# MCU_Core.net
KiCad netlist of a schematic drawn in Altium Designer
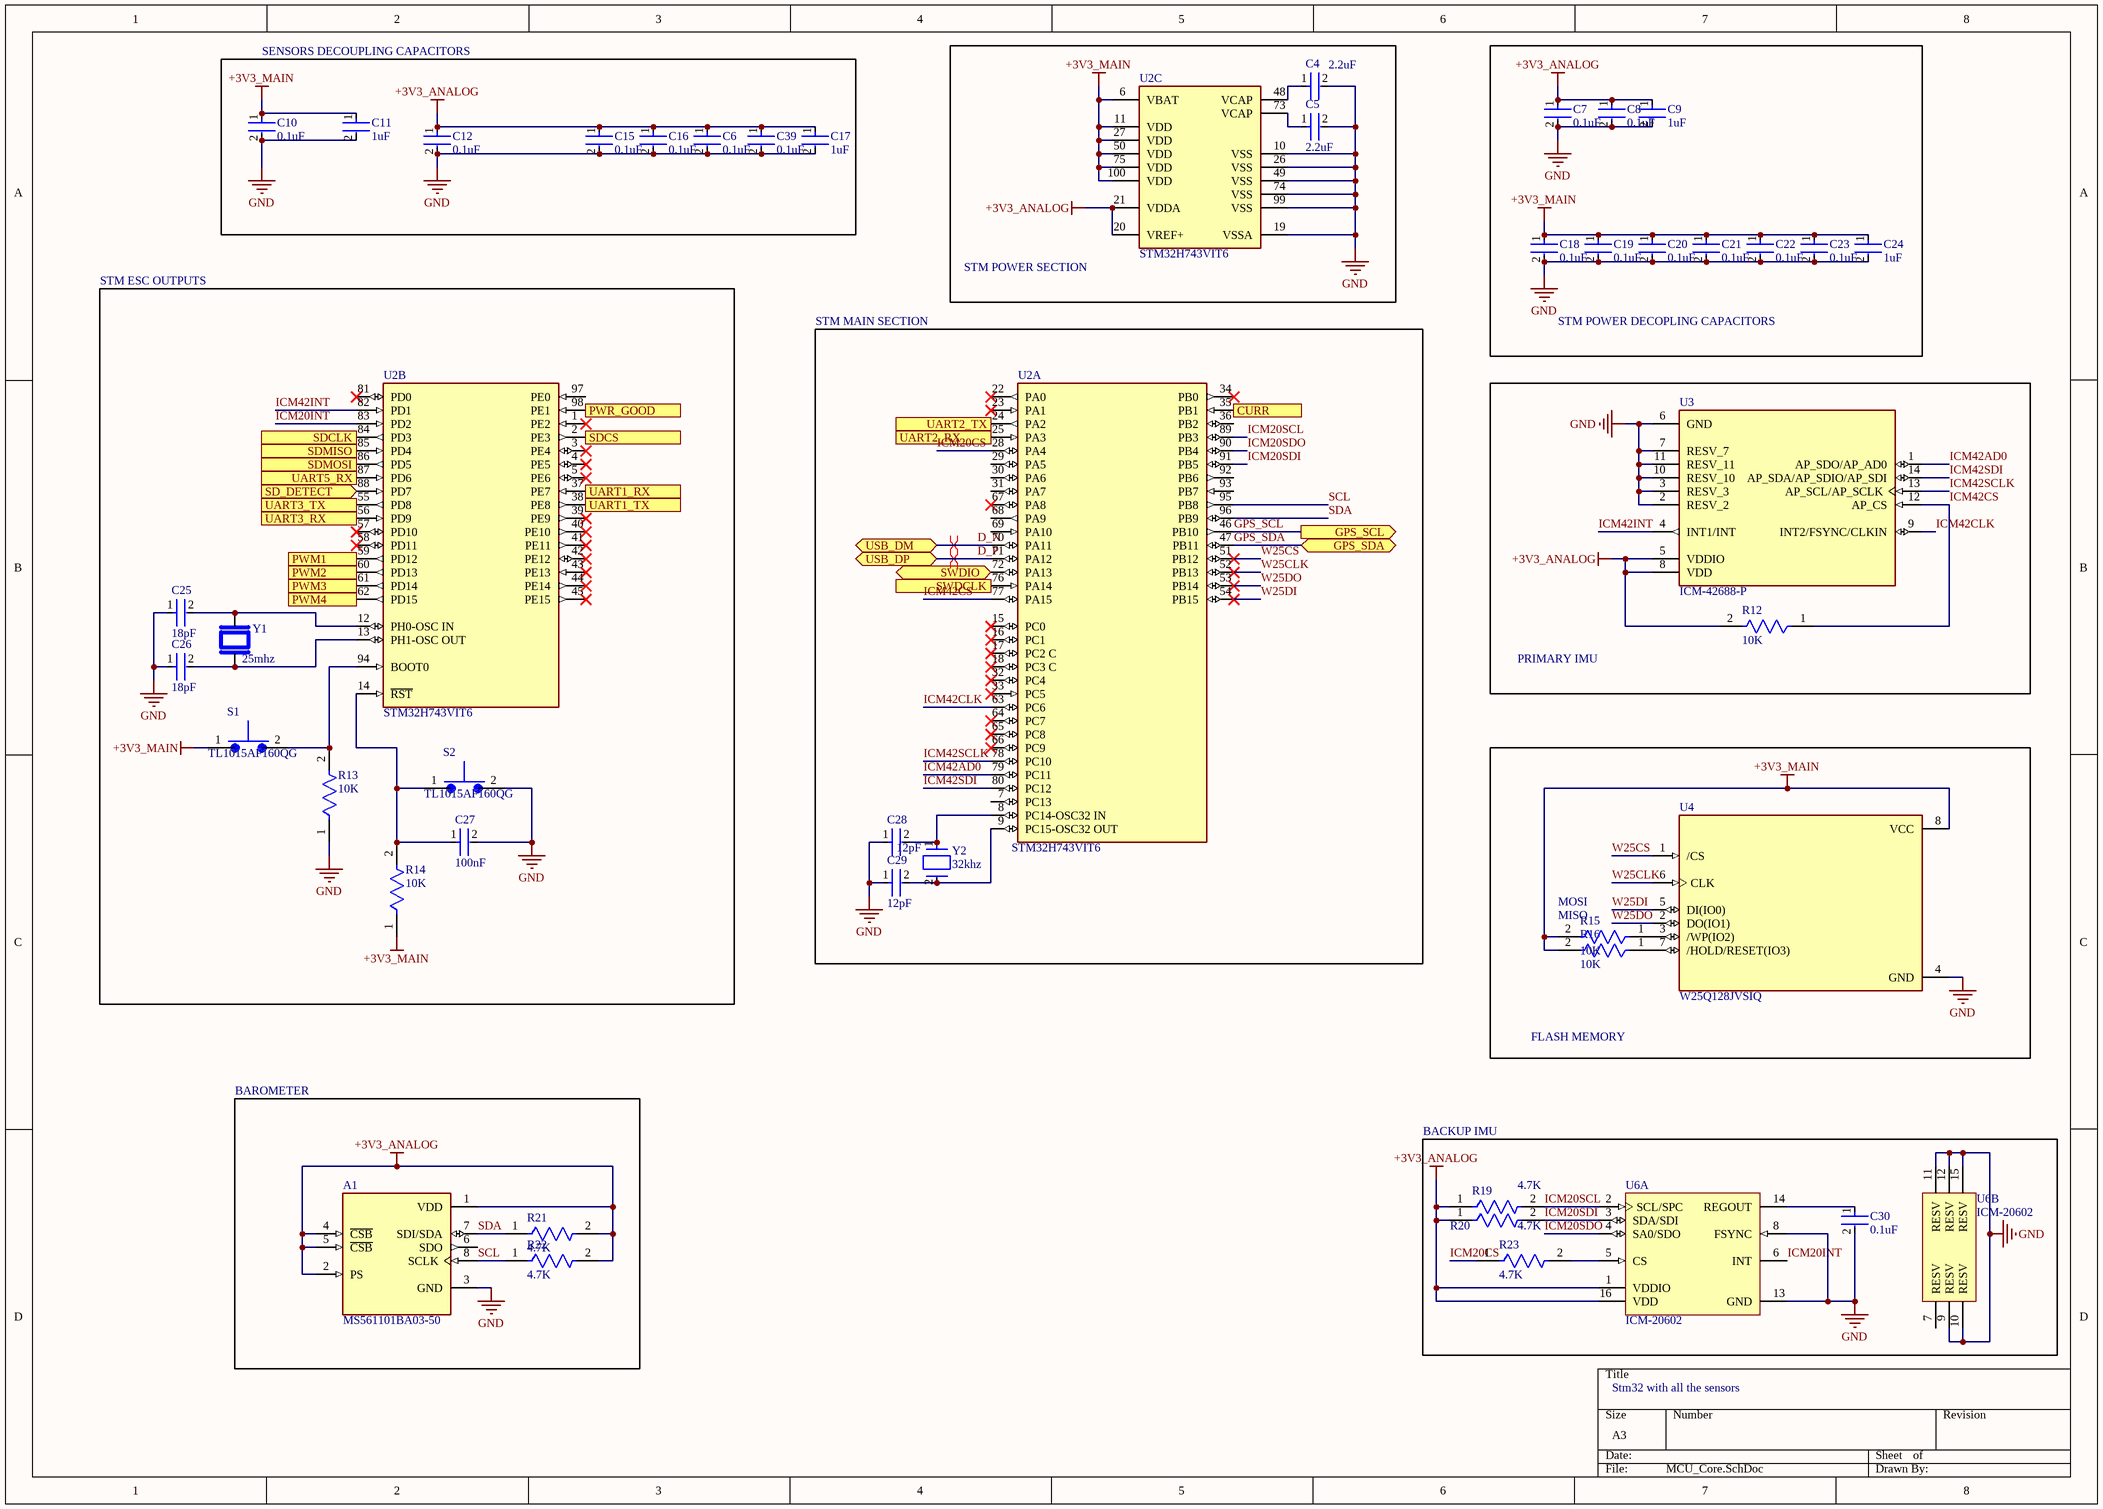
[diagram p0: MCU_Core.SchDoc]

(export (version "E")
  (design (tool "Eeschema 10.0.6"))
  (components
    (comp (ref "A1")
      (value "MS561101BA03-50")
      (footprint "XDCR_MS561101BA03-50")
      (description "Sensor;MS5611-BT M-CAPS 3X5X1MM T&R;Pressure;MS561101BA03-50 ¦ TE Connectivity MS561101BA03-50")
      (fields (field (name "MF") "TE Connectivity"))
      (libsource (lib "MS561101BA03-50") (part "MS561101BA03-50"))
    )
    (comp (ref "C4")
      (value "2.2uF")
      (footprint "FP-GRM155-0_15-IPC_A")
      (description "Chip Multilayer Ceramic Capacitors for General Purpose, 0402, 2.2uF, X7R, 15%, 10%, 10V")
      (libsource (lib "Altium Content Vault") (part "b4654b650e69147ec39a6b967a45e02"))
    )
    (comp (ref "C5")
      (value "2.2uF")
      (footprint "FP-GRM155-0_15-IPC_A")
      (description "Chip Multilayer Ceramic Capacitors for General Purpose, 0402, 2.2uF, X7R, 15%, 10%, 10V")
      (libsource (lib "Altium Content Vault") (part "b4654b650e69147ec39a6b967a45e02"))
    )
    (comp (ref "C6")
      (value "0.1uF")
      (footprint "FP-C0402-BB-MFG")
      (description "CAP CER 0.1UF 10V X7R 0402")
      (fields (field (name "MANUFACTURER") "Kemet") (field (name "TOLERANCE") "0.1"))
      (libsource (lib "Altium Content Vault") (part "b4654b650e69147ec39a6b967a45e02"))
    )
    (comp (ref "C7")
      (value "0.1uF")
      (footprint "FP-C0402-BB-MFG")
      (description "CAP CER 0.1UF 10V X7R 0402")
      (fields (field (name "MANUFACTURER") "Kemet") (field (name "TOLERANCE") "0.1"))
      (libsource (lib "Altium Content Vault") (part "b4654b650e69147ec39a6b967a45e02"))
    )
    (comp (ref "C8")
      (value "0.1uF")
      (footprint "FP-C0402-BB-MFG")
      (description "CAP CER 0.1UF 10V X7R 0402")
      (fields (field (name "MANUFACTURER") "Kemet") (field (name "TOLERANCE") "0.1"))
      (libsource (lib "Altium Content Vault") (part "b4654b650e69147ec39a6b967a45e02"))
    )
    (comp (ref "C9")
      (value "1uF")
      (footprint "FP-GRM152-0_05-MFG")
      (description "Chip Multilayer Ceramic Capacitors for General Purpose, 0402, 1.0uF, X5R, 15%, 20%, 6.3V")
      (fields (field (name "TOLERANCE") "20%"))
      (libsource (lib "Altium Content Vault") (part "b4654b650e69147ec39a6b967a45e02"))
    )
    (comp (ref "C10")
      (value "0.1uF")
      (footprint "FP-C0402-BB-MFG")
      (description "CAP CER 0.1UF 10V X7R 0402")
      (fields (field (name "MANUFACTURER") "Kemet") (field (name "TOLERANCE") "0.1"))
      (libsource (lib "Altium Content Vault") (part "b4654b650e69147ec39a6b967a45e02"))
    )
    (comp (ref "C11")
      (value "1uF")
      (footprint "FP-GRM152-0_05-MFG")
      (description "Chip Multilayer Ceramic Capacitors for General Purpose, 0402, 1.0uF, X5R, 15%, 20%, 6.3V")
      (fields (field (name "TOLERANCE") "20%"))
      (libsource (lib "Altium Content Vault") (part "b4654b650e69147ec39a6b967a45e02"))
    )
    (comp (ref "C12")
      (value "0.1uF")
      (footprint "FP-C0402-BB-MFG")
      (description "CAP CER 0.1UF 10V X7R 0402")
      (fields (field (name "MANUFACTURER") "Kemet") (field (name "TOLERANCE") "0.1"))
      (libsource (lib "Altium Content Vault") (part "b4654b650e69147ec39a6b967a45e02"))
    )
    (comp (ref "C15")
      (value "0.1uF")
      (footprint "FP-C0402-BB-MFG")
      (description "CAP CER 0.1UF 10V X7R 0402")
      (fields (field (name "MANUFACTURER") "Kemet") (field (name "TOLERANCE") "0.1"))
      (libsource (lib "Altium Content Vault") (part "b4654b650e69147ec39a6b967a45e02"))
    )
    (comp (ref "C16")
      (value "0.1uF")
      (footprint "FP-C0402-BB-MFG")
      (description "CAP CER 0.1UF 10V X7R 0402")
      (fields (field (name "MANUFACTURER") "Kemet") (field (name "TOLERANCE") "0.1"))
      (libsource (lib "Altium Content Vault") (part "b4654b650e69147ec39a6b967a45e02"))
    )
    (comp (ref "C17")
      (value "1uF")
      (footprint "FP-GRM152-0_05-MFG")
      (description "Chip Multilayer Ceramic Capacitors for General Purpose, 0402, 1.0uF, X5R, 15%, 20%, 6.3V")
      (fields (field (name "TOLERANCE") "20%"))
      (libsource (lib "Altium Content Vault") (part "b4654b650e69147ec39a6b967a45e02"))
    )
    (comp (ref "C18")
      (value "0.1uF")
      (footprint "FP-C0402-BB-MFG")
      (description "CAP CER 0.1UF 10V X7R 0402")
      (fields (field (name "MANUFACTURER") "Kemet") (field (name "TOLERANCE") "0.1"))
      (libsource (lib "Altium Content Vault") (part "b4654b650e69147ec39a6b967a45e02"))
    )
    (comp (ref "C19")
      (value "0.1uF")
      (footprint "FP-C0402-BB-MFG")
      (description "CAP CER 0.1UF 10V X7R 0402")
      (fields (field (name "MANUFACTURER") "Kemet") (field (name "TOLERANCE") "0.1"))
      (libsource (lib "Altium Content Vault") (part "b4654b650e69147ec39a6b967a45e02"))
    )
    (comp (ref "C20")
      (value "0.1uF")
      (footprint "FP-C0402-BB-MFG")
      (description "CAP CER 0.1UF 10V X7R 0402")
      (fields (field (name "MANUFACTURER") "Kemet") (field (name "TOLERANCE") "0.1"))
      (libsource (lib "Altium Content Vault") (part "b4654b650e69147ec39a6b967a45e02"))
    )
    (comp (ref "C21")
      (value "0.1uF")
      (footprint "FP-C0402-BB-MFG")
      (description "CAP CER 0.1UF 10V X7R 0402")
      (fields (field (name "MANUFACTURER") "Kemet") (field (name "TOLERANCE") "0.1"))
      (libsource (lib "Altium Content Vault") (part "b4654b650e69147ec39a6b967a45e02"))
    )
    (comp (ref "C22")
      (value "0.1uF")
      (footprint "FP-C0402-BB-MFG")
      (description "CAP CER 0.1UF 10V X7R 0402")
      (fields (field (name "MANUFACTURER") "Kemet") (field (name "TOLERANCE") "0.1"))
      (libsource (lib "Altium Content Vault") (part "b4654b650e69147ec39a6b967a45e02"))
    )
    (comp (ref "C23")
      (value "0.1uF")
      (footprint "FP-C0402-BB-MFG")
      (description "CAP CER 0.1UF 10V X7R 0402")
      (fields (field (name "MANUFACTURER") "Kemet") (field (name "TOLERANCE") "0.1"))
      (libsource (lib "Altium Content Vault") (part "b4654b650e69147ec39a6b967a45e02"))
    )
    (comp (ref "C24")
      (value "1uF")
      (footprint "FP-GRM152-0_05-MFG")
      (description "Chip Multilayer Ceramic Capacitors for General Purpose, 0402, 1.0uF, X5R, 15%, 20%, 6.3V")
      (fields (field (name "TOLERANCE") "20%"))
      (libsource (lib "Altium Content Vault") (part "b4654b650e69147ec39a6b967a45e02"))
    )
    (comp (ref "C25")
      (value "18pF")
      (footprint "FP-C0402-BB-MFG")
      (description "C0402 18 pF X8R 5.00% 50 V")
      (fields
        (field (name "OCTOPART") "https://octopart.com/c0402c180j5hacauto-kemet-88080534")
        (field (name "MANUFACTURER") "Kemet")
      )
      (libsource (lib "Altium Content Vault") (part "b4654b650e69147ec39a6b967a45e02"))
    )
    (comp (ref "C26")
      (value "18pF")
      (footprint "FP-C0402-BB-MFG")
      (description "C0402 18 pF X8R 5.00% 50 V")
      (fields
        (field (name "OCTOPART") "https://octopart.com/c0402c180j5hacauto-kemet-88080534")
        (field (name "MANUFACTURER") "Kemet")
      )
      (libsource (lib "Altium Content Vault") (part "b4654b650e69147ec39a6b967a45e02"))
    )
    (comp (ref "C27")
      (value "100nF")
      (footprint "FP-C0402-BB-MFG")
      (description "CAP CER 0.1UF 10V X7R 0402")
      (fields (field (name "MANUFACTURER") "Kemet") (field (name "TOLERANCE") "0.1"))
      (libsource (lib "Altium Content Vault") (part "b4654b650e69147ec39a6b967a45e02"))
    )
    (comp (ref "C28")
      (value "12pF")
      (footprint "FP-C0402-BB-MFG")
      (description "C0402 12 pF X8R 5.00% 50 V")
      (fields (field (name "TOLERANCE") "0.05") (field (name "MANUFACTURER") "Kemet"))
      (libsource (lib "Altium Content Vault") (part "b4654b650e69147ec39a6b967a45e02"))
    )
    (comp (ref "C29")
      (value "12pF")
      (footprint "FP-C0402-BB-MFG")
      (description "C0402 12 pF X8R 5.00% 50 V")
      (fields (field (name "TOLERANCE") "0.05") (field (name "MANUFACTURER") "Kemet"))
      (libsource (lib "Altium Content Vault") (part "b4654b650e69147ec39a6b967a45e02"))
    )
    (comp (ref "C30")
      (value "0.1uF")
      (footprint "FP-C0402-BB-MFG")
      (description "CAP CER 0.1UF 10V X7R 0402")
      (fields (field (name "MANUFACTURER") "Kemet") (field (name "TOLERANCE") "0.1"))
      (libsource (lib "Altium Content Vault") (part "b4654b650e69147ec39a6b967a45e02"))
    )
    (comp (ref "C39")
      (value "0.1uF")
      (footprint "FP-C0402-BB-MFG")
      (description "CAP CER 0.1UF 10V X7R 0402")
      (fields (field (name "MANUFACTURER") "Kemet") (field (name "TOLERANCE") "0.1"))
      (libsource (lib "Altium Content Vault") (part "b4654b650e69147ec39a6b967a45e02"))
    )
    (comp (ref "R12")
      (value "10K")
      (footprint "FP-MCS0402-MFG")
      (description "RES SMD 1.2K OHM 1% 1/10W 0402")
      (fields (field (name "TOLERANCE") "0.5%"))
      (libsource (lib "Altium Content Vault") (part "1029c3af85768c4190bb7ad29bc67b5"))
    )
    (comp (ref "R13")
      (value "10K")
      (footprint "FP-MCS0402-MFG")
      (description "RES SMD 1.2K OHM 1% 1/10W 0402")
      (fields (field (name "TOLERANCE") "0.5%"))
      (libsource (lib "Altium Content Vault") (part "1029c3af85768c4190bb7ad29bc67b5"))
    )
    (comp (ref "R14")
      (value "10K")
      (footprint "FP-MCS0402-MFG")
      (description "RES SMD 1.2K OHM 1% 1/10W 0402")
      (fields (field (name "TOLERANCE") "0.5%"))
      (libsource (lib "Altium Content Vault") (part "1029c3af85768c4190bb7ad29bc67b5"))
    )
    (comp (ref "R15")
      (value "10K")
      (footprint "FP-MCS0402-MFG")
      (description "RES SMD 1.2K OHM 1% 1/10W 0402")
      (fields (field (name "TOLERANCE") "0.5%"))
      (libsource (lib "Altium Content Vault") (part "1029c3af85768c4190bb7ad29bc67b5"))
    )
    (comp (ref "R16")
      (value "10K")
      (footprint "FP-MCS0402-MFG")
      (description "RES SMD 1.2K OHM 1% 1/10W 0402")
      (fields (field (name "TOLERANCE") "0.5%"))
      (libsource (lib "Altium Content Vault") (part "1029c3af85768c4190bb7ad29bc67b5"))
    )
    (comp (ref "R19")
      (value "4.7K")
      (footprint "FP-CRCW0402-Pe3-IPC_C")
      (description "RES Thick Film, 4.7kΩ, 1%, 0.063W, 50ppm/°C, 0402")
      (fields (field (name "TOLERANCE") "1%"))
      (libsource (lib "Altium Content Vault") (part "1029c3af85768c4190bb7ad29bc67b5"))
    )
    (comp (ref "R20")
      (value "4.7K")
      (footprint "FP-CRCW0402-Pe3-IPC_C")
      (description "RES Thick Film, 4.7kΩ, 1%, 0.063W, 50ppm/°C, 0402")
      (fields (field (name "TOLERANCE") "1%"))
      (libsource (lib "Altium Content Vault") (part "1029c3af85768c4190bb7ad29bc67b5"))
    )
    (comp (ref "R21")
      (value "4.7K")
      (footprint "FP-CRCW0402-Pe3-IPC_C")
      (description "RES Thick Film, 4.7kΩ, 1%, 0.063W, 50ppm/°C, 0402")
      (fields (field (name "TOLERANCE") "1%"))
      (libsource (lib "Altium Content Vault") (part "1029c3af85768c4190bb7ad29bc67b5"))
    )
    (comp (ref "R22")
      (value "4.7K")
      (footprint "FP-CRCW0402-Pe3-IPC_C")
      (description "RES Thick Film, 4.7kΩ, 1%, 0.063W, 50ppm/°C, 0402")
      (fields (field (name "TOLERANCE") "1%"))
      (libsource (lib "Altium Content Vault") (part "1029c3af85768c4190bb7ad29bc67b5"))
    )
    (comp (ref "R23")
      (value "4.7K")
      (footprint "FP-CRCW0402-Pe3-IPC_C")
      (description "RES Thick Film, 4.7kΩ, 1%, 0.063W, 50ppm/°C, 0402")
      (fields (field (name "TOLERANCE") "1%"))
      (libsource (lib "Altium Content Vault") (part "1029c3af85768c4190bb7ad29bc67b5"))
    )
    (comp (ref "S1")
      (value "TL1015AF160QG")
      (footprint "SW_TL1015AF160QG")
      (description "Tactile Switch SPST-NO Top Actuated Surface Mount")
      (libsource (lib "3x4mm tactile switch") (part "TL1015AF160QG"))
    )
    (comp (ref "S2")
      (value "TL1015AF160QG")
      (footprint "SW_TL1015AF160QG")
      (description "Tactile Switch SPST-NO Top Actuated Surface Mount")
      (libsource (lib "3x4mm tactile switch") (part "TL1015AF160QG"))
    )
    (comp (ref "U2")
      (value "STM32H743VIT6")
      (footprint "FP-LQFP100-1L-MFG")
      (description "IC MCU 32BIT 2MB FLASH 100LQFP")
      (fields
        (field (name "OCTOPART") "https://octopart.com/stm32h743vit6-stmicroelectronics-76372527")
        (field (name "MANUFACTURER") "STMicroelectronics")
      )
      (libsource (lib "Altium Content Vault") (part "01082ce2885d1d16a22823c45526fe6"))
    )
    (comp (ref "U3")
      (value "ICM-42688-P")
      (footprint "PQFN50P300X250X97-14N")
      (description "Accelerometer, Gyroscope, 6 Axis Sensor Output")
      (libsource (lib "ICM-42688-P") (part "ICM-42688-P"))
    )
    (comp (ref "U4")
      (value "W25Q128JVSIQ")
      (footprint "SOIC127P790X216-8N")
      (description "FLASH - NOR Memory IC 128Mb (16M x 8) SPI - Quad I/O, QPI, DTR 133 MHz 8-SOIC")
      (fields (field (name "MF") "Winbond Electronics"))
      (libsource (lib "W25Q128JVSIQ") (part "W25Q128JVSIQ"))
    )
    (comp (ref "U6")
      (value "ICM-20602")
      (footprint "INSE-I62-16")
      (fields (field (name "MANUFACTURER") "InvenSense"))
      (libsource (lib "") (part "INSE-ICM-20602-16_1"))
    )
    (comp (ref "Y1")
      (value "25mhz")
      (footprint "XTAL_SXT32412BB07-25.000MT")
      (description "25 MHz Â±30ppm Crystal 12pF 50 Ohms 4-SMD, No Lead")
      (fields (field (name "MF") "Suntsu") (field (name "MP") "SXT32412BB07-25.000M"))
      (libsource (lib "SXT32412BB07-25.000MT") (part "SXT32412BB07-25.000MT"))
    )
    (comp (ref "Y2")
      (value "32khz")
      (footprint "FP-ABS07-MFG")
      (description "Crystal 32.768kHz ±20ppm (Tol) 12.5pF FUND 70kΩ 2-Pin CSMD T/R")
      (fields (field (name "TOLERANCE") "20ppm"))
      (libsource (lib "Altium Content Vault") (part "c23a69dc6c9e2f18f2079038eb95dd1"))
    )
  )
  (nets
    (net (code "1") (name "+3V3_ANALOG") (class "Default")
      (node (ref "A1") (pin "1") (pinfunction "VDD_1") (pintype "power_in"))
      (node (ref "A1") (pin "2") (pinfunction "PS_2") (pintype "input"))
      (node (ref "A1") (pin "4") (pinfunction "~{CSB}_4") (pintype "input"))
      (node (ref "A1") (pin "5") (pinfunction "~{CSB}_5") (pintype "input"))
      (node (ref "C12") (pin "1") (pinfunction "1_1") (pintype "passive"))
      (node (ref "C15") (pin "1") (pinfunction "1_1") (pintype "passive"))
      (node (ref "C16") (pin "1") (pinfunction "1_1") (pintype "passive"))
      (node (ref "C17") (pin "1") (pinfunction "1_1") (pintype "passive"))
      (node (ref "C39") (pin "1") (pinfunction "1_1") (pintype "passive"))
      (node (ref "C6") (pin "1") (pinfunction "1_1") (pintype "passive"))
      (node (ref "C7") (pin "1") (pinfunction "1_1") (pintype "passive"))
      (node (ref "C8") (pin "1") (pinfunction "1_1") (pintype "passive"))
      (node (ref "C9") (pin "1") (pinfunction "1_1") (pintype "passive"))
      (node (ref "R12") (pin "2") (pinfunction "2_2") (pintype "passive"))
      (node (ref "R19") (pin "1") (pinfunction "1_1") (pintype "passive"))
      (node (ref "R20") (pin "1") (pinfunction "1_1") (pintype "passive"))
      (node (ref "R21") (pin "2") (pinfunction "2_2") (pintype "passive"))
      (node (ref "R22") (pin "2") (pinfunction "2_2") (pintype "passive"))
      (node (ref "U2") (pin "20") (pinfunction "VREF+_20") (pintype "power_in"))
      (node (ref "U2") (pin "21") (pinfunction "VDDA_21") (pintype "power_in"))
      (node (ref "U3") (pin "5") (pinfunction "VDDIO_5") (pintype "power_in"))
      (node (ref "U3") (pin "8") (pinfunction "VDD_8") (pintype "power_in"))
      (node (ref "U6") (pin "1") (pinfunction "VDDIO_1") (pintype "power_in"))
      (node (ref "U6") (pin "16") (pinfunction "VDD_16") (pintype "power_in"))
    )
    (net (code "2") (name "+3V3_MAIN") (class "Default")
      (node (ref "C10") (pin "1") (pinfunction "1_1") (pintype "passive"))
      (node (ref "C11") (pin "1") (pinfunction "1_1") (pintype "passive"))
      (node (ref "C18") (pin "1") (pinfunction "1_1") (pintype "passive"))
      (node (ref "C19") (pin "1") (pinfunction "1_1") (pintype "passive"))
      (node (ref "C20") (pin "1") (pinfunction "1_1") (pintype "passive"))
      (node (ref "C21") (pin "1") (pinfunction "1_1") (pintype "passive"))
      (node (ref "C22") (pin "1") (pinfunction "1_1") (pintype "passive"))
      (node (ref "C23") (pin "1") (pinfunction "1_1") (pintype "passive"))
      (node (ref "C24") (pin "1") (pinfunction "1_1") (pintype "passive"))
      (node (ref "R14") (pin "1") (pinfunction "1_1") (pintype "passive"))
      (node (ref "R15") (pin "2") (pinfunction "2_2") (pintype "passive"))
      (node (ref "R16") (pin "2") (pinfunction "2_2") (pintype "passive"))
      (node (ref "S1") (pin "1") (pinfunction "1_1") (pintype "passive"))
      (node (ref "U2") (pin "100") (pinfunction "VDD_100") (pintype "power_in"))
      (node (ref "U2") (pin "11") (pinfunction "VDD_11") (pintype "power_in"))
      (node (ref "U2") (pin "27") (pinfunction "VDD_27") (pintype "power_in"))
      (node (ref "U2") (pin "50") (pinfunction "VDD_50") (pintype "power_in"))
      (node (ref "U2") (pin "6") (pinfunction "VBAT_6") (pintype "power_in"))
      (node (ref "U2") (pin "75") (pinfunction "VDD_75") (pintype "power_in"))
      (node (ref "U4") (pin "8") (pinfunction "VCC_8") (pintype "power_in"))
    )
    (net (code "3") (name "/CURR") (class "Default")
      (node (ref "U2") (pin "35") (pinfunction "PB1_35") (pintype "bidirectional"))
    )
    (net (code "4") (name "/D_N") (class "Default")
      (node (ref "U2") (pin "70") (pinfunction "PA11_70") (pintype "bidirectional"))
    )
    (net (code "5") (name "/D_P") (class "Default")
      (node (ref "U2") (pin "71") (pinfunction "PA12_71") (pintype "bidirectional"))
    )
    (net (code "6") (name "/GPS_SCL") (class "Default")
      (node (ref "U2") (pin "46") (pinfunction "PB10_46") (pintype "bidirectional"))
    )
    (net (code "7") (name "/GPS_SDA") (class "Default")
      (node (ref "U2") (pin "47") (pinfunction "PB11_47") (pintype "bidirectional"))
    )
    (net (code "8") (name "/ICM20CS") (class "Default")
      (node (ref "R23") (pin "1") (pinfunction "1_1") (pintype "passive"))
      (node (ref "U2") (pin "28") (pinfunction "PA4_28") (pintype "bidirectional"))
    )
    (net (code "9") (name "/ICM20INT") (class "Default")
      (node (ref "U2") (pin "83") (pinfunction "PD2_83") (pintype "input"))
      (node (ref "U6") (pin "6") (pinfunction "INT_6") (pintype "open_collector"))
    )
    (net (code "10") (name "/ICM20SCL") (class "Default")
      (node (ref "R19") (pin "2") (pinfunction "2_2") (pintype "passive"))
      (node (ref "U2") (pin "89") (pinfunction "PB3_89") (pintype "bidirectional"))
      (node (ref "U6") (pin "2") (pinfunction "SCL/SPC_2") (pintype "input"))
    )
    (net (code "11") (name "/ICM20SDI") (class "Default")
      (node (ref "R20") (pin "2") (pinfunction "2_2") (pintype "passive"))
      (node (ref "U2") (pin "91") (pinfunction "PB5_91") (pintype "bidirectional"))
      (node (ref "U6") (pin "3") (pinfunction "SDA/SDI_3") (pintype "bidirectional"))
    )
    (net (code "12") (name "/ICM20SDO") (class "Default")
      (node (ref "U2") (pin "90") (pinfunction "PB4_90") (pintype "bidirectional"))
      (node (ref "U6") (pin "4") (pinfunction "SA0/SDO_4") (pintype "bidirectional"))
    )
    (net (code "13") (name "/ICM42AD0") (class "Default")
      (node (ref "U2") (pin "79") (pinfunction "PC11_79") (pintype "bidirectional"))
      (node (ref "U3") (pin "1") (pinfunction "AP_SDO/AP_AD0_1") (pintype "bidirectional"))
    )
    (net (code "14") (name "/ICM42CLK") (class "Default")
      (node (ref "U2") (pin "63") (pinfunction "PC6_63") (pintype "bidirectional"))
      (node (ref "U3") (pin "9") (pinfunction "INT2/FSYNC/CLKIN_9") (pintype "bidirectional"))
    )
    (net (code "15") (name "/ICM42CS") (class "Default")
      (node (ref "R12") (pin "1") (pinfunction "1_1") (pintype "passive"))
      (node (ref "U2") (pin "77") (pinfunction "PA15_77") (pintype "bidirectional"))
      (node (ref "U3") (pin "12") (pinfunction "AP_CS_12") (pintype "input"))
    )
    (net (code "16") (name "/ICM42INT") (class "Default")
      (node (ref "U2") (pin "82") (pinfunction "PD1_82") (pintype "input"))
      (node (ref "U3") (pin "4") (pinfunction "INT1/INT_4") (pintype "output"))
    )
    (net (code "17") (name "/ICM42SCLK") (class "Default")
      (node (ref "U2") (pin "78") (pinfunction "PC10_78") (pintype "bidirectional"))
      (node (ref "U3") (pin "13") (pinfunction "AP_SCL/AP_SCLK_13") (pintype "input"))
    )
    (net (code "18") (name "/ICM42SDI") (class "Default")
      (node (ref "U2") (pin "80") (pinfunction "PC12_80") (pintype "bidirectional"))
      (node (ref "U3") (pin "14") (pinfunction "AP_SDA/AP_SDIO/AP_SDI_14") (pintype "bidirectional"))
    )
    (net (code "19") (name "/PWM1") (class "Default")
      (node (ref "U2") (pin "59") (pinfunction "PD12_59") (pintype "output"))
    )
    (net (code "20") (name "/PWM2") (class "Default")
      (node (ref "U2") (pin "60") (pinfunction "PD13_60") (pintype "output"))
    )
    (net (code "21") (name "/PWM3") (class "Default")
      (node (ref "U2") (pin "61") (pinfunction "PD14_61") (pintype "output"))
    )
    (net (code "22") (name "/PWM4") (class "Default")
      (node (ref "U2") (pin "62") (pinfunction "PD15_62") (pintype "output"))
    )
    (net (code "23") (name "/PWR_GOOD") (class "Default")
      (node (ref "U2") (pin "98") (pinfunction "PE1_98") (pintype "input"))
    )
    (net (code "24") (name "/SCL") (class "Default")
      (node (ref "A1") (pin "8") (pinfunction "SCLK_8") (pintype "input"))
      (node (ref "R22") (pin "1") (pinfunction "1_1") (pintype "passive"))
      (node (ref "U2") (pin "95") (pinfunction "PB8_95") (pintype "bidirectional"))
    )
    (net (code "25") (name "/SDA") (class "Default")
      (node (ref "A1") (pin "7") (pinfunction "SDI/SDA_7") (pintype "bidirectional"))
      (node (ref "R21") (pin "1") (pinfunction "1_1") (pintype "passive"))
      (node (ref "U2") (pin "96") (pinfunction "PB9_96") (pintype "bidirectional"))
    )
    (net (code "26") (name "/SDCLK") (class "Default")
      (node (ref "U2") (pin "84") (pinfunction "PD3_84") (pintype "output"))
    )
    (net (code "27") (name "/SDCS") (class "Default")
      (node (ref "U2") (pin "2") (pinfunction "PE3_2") (pintype "output"))
    )
    (net (code "28") (name "/SDMISO") (class "Default")
      (node (ref "U2") (pin "85") (pinfunction "PD4_85") (pintype "input"))
    )
    (net (code "29") (name "/SDMOSI") (class "Default")
      (node (ref "U2") (pin "86") (pinfunction "PD5_86") (pintype "output"))
    )
    (net (code "30") (name "/SD_DETECT") (class "Default")
      (node (ref "U2") (pin "88") (pinfunction "PD7_88") (pintype "input"))
    )
    (net (code "31") (name "/SWDCLK") (class "Default")
      (node (ref "U2") (pin "76") (pinfunction "PA14_76") (pintype "bidirectional"))
    )
    (net (code "32") (name "/SWDIO") (class "Default")
      (node (ref "U2") (pin "72") (pinfunction "PA13_72") (pintype "bidirectional"))
    )
    (net (code "33") (name "/UART1_RX") (class "Default")
      (node (ref "U2") (pin "37") (pinfunction "PE7_37") (pintype "input"))
    )
    (net (code "34") (name "/UART1_TX") (class "Default")
      (node (ref "U2") (pin "38") (pinfunction "PE8_38") (pintype "output"))
    )
    (net (code "35") (name "/UART2_RX") (class "Default")
      (node (ref "U2") (pin "25") (pinfunction "PA3_25") (pintype "bidirectional"))
    )
    (net (code "36") (name "/UART2_TX") (class "Default")
      (node (ref "U2") (pin "24") (pinfunction "PA2_24") (pintype "bidirectional"))
    )
    (net (code "37") (name "/UART3_RX") (class "Default")
      (node (ref "U2") (pin "56") (pinfunction "PD9_56") (pintype "input"))
    )
    (net (code "38") (name "/UART3_TX") (class "Default")
      (node (ref "U2") (pin "55") (pinfunction "PD8_55") (pintype "output"))
    )
    (net (code "39") (name "/UART5_RX") (class "Default")
      (node (ref "U2") (pin "87") (pinfunction "PD6_87") (pintype "input"))
    )
    (net (code "40") (name "/W25CLK") (class "Default")
      (node (ref "U2") (pin "52") (pinfunction "PB13_52") (pintype "bidirectional"))
      (node (ref "U4") (pin "6") (pinfunction "CLK_6") (pintype "input"))
    )
    (net (code "41") (name "/W25CS") (class "Default")
      (node (ref "U2") (pin "51") (pinfunction "PB12_51") (pintype "bidirectional"))
      (node (ref "U4") (pin "1") (pinfunction "/CS_1") (pintype "input"))
    )
    (net (code "42") (name "/W25DI") (class "Default")
      (node (ref "U2") (pin "54") (pinfunction "PB15_54") (pintype "bidirectional"))
      (node (ref "U4") (pin "5") (pinfunction "DI(IO0)_5") (pintype "bidirectional"))
    )
    (net (code "43") (name "/W25DO") (class "Default")
      (node (ref "U2") (pin "53") (pinfunction "PB14_53") (pintype "bidirectional"))
      (node (ref "U4") (pin "2") (pinfunction "DO(IO1)_2") (pintype "bidirectional"))
    )
    (net (code "44") (name "GND") (class "Default")
      (node (ref "A1") (pin "3") (pinfunction "GND_3") (pintype "power_in"))
      (node (ref "C10") (pin "2") (pinfunction "2_2") (pintype "passive"))
      (node (ref "C11") (pin "2") (pinfunction "2_2") (pintype "passive"))
      (node (ref "C12") (pin "2") (pinfunction "2_2") (pintype "passive"))
      (node (ref "C15") (pin "2") (pinfunction "2_2") (pintype "passive"))
      (node (ref "C16") (pin "2") (pinfunction "2_2") (pintype "passive"))
      (node (ref "C17") (pin "2") (pinfunction "2_2") (pintype "passive"))
      (node (ref "C18") (pin "2") (pinfunction "2_2") (pintype "passive"))
      (node (ref "C19") (pin "2") (pinfunction "2_2") (pintype "passive"))
      (node (ref "C20") (pin "2") (pinfunction "2_2") (pintype "passive"))
      (node (ref "C21") (pin "2") (pinfunction "2_2") (pintype "passive"))
      (node (ref "C22") (pin "2") (pinfunction "2_2") (pintype "passive"))
      (node (ref "C23") (pin "2") (pinfunction "2_2") (pintype "passive"))
      (node (ref "C24") (pin "2") (pinfunction "2_2") (pintype "passive"))
      (node (ref "C25") (pin "1") (pinfunction "1_1") (pintype "passive"))
      (node (ref "C26") (pin "1") (pinfunction "1_1") (pintype "passive"))
      (node (ref "C27") (pin "2") (pinfunction "2_2") (pintype "passive"))
      (node (ref "C28") (pin "1") (pinfunction "1_1") (pintype "passive"))
      (node (ref "C29") (pin "1") (pinfunction "1_1") (pintype "passive"))
      (node (ref "C30") (pin "2") (pinfunction "2_2") (pintype "passive"))
      (node (ref "C39") (pin "2") (pinfunction "2_2") (pintype "passive"))
      (node (ref "C4") (pin "2") (pinfunction "2_2") (pintype "passive"))
      (node (ref "C5") (pin "2") (pinfunction "2_2") (pintype "passive"))
      (node (ref "C6") (pin "2") (pinfunction "2_2") (pintype "passive"))
      (node (ref "C7") (pin "2") (pinfunction "2_2") (pintype "passive"))
      (node (ref "C8") (pin "2") (pinfunction "2_2") (pintype "passive"))
      (node (ref "C9") (pin "2") (pinfunction "2_2") (pintype "passive"))
      (node (ref "R13") (pin "1") (pinfunction "1_1") (pintype "passive"))
      (node (ref "S2") (pin "2") (pinfunction "2_2") (pintype "passive"))
      (node (ref "U2") (pin "10") (pinfunction "VSS_10") (pintype "power_in"))
      (node (ref "U2") (pin "19") (pinfunction "VSSA_19") (pintype "power_in"))
      (node (ref "U2") (pin "26") (pinfunction "VSS_26") (pintype "power_in"))
      (node (ref "U2") (pin "49") (pinfunction "VSS_49") (pintype "power_in"))
      (node (ref "U2") (pin "74") (pinfunction "VSS_74") (pintype "power_in"))
      (node (ref "U2") (pin "99") (pinfunction "VSS_99") (pintype "power_in"))
      (node (ref "U3") (pin "10") (pinfunction "RESV_10_10") (pintype "passive"))
      (node (ref "U3") (pin "11") (pinfunction "RESV_11_11") (pintype "passive"))
      (node (ref "U3") (pin "2") (pinfunction "RESV_2_2") (pintype "passive"))
      (node (ref "U3") (pin "3") (pinfunction "RESV_3_3") (pintype "passive"))
      (node (ref "U3") (pin "6") (pinfunction "GND_6") (pintype "power_in"))
      (node (ref "U3") (pin "7") (pinfunction "RESV_7_7") (pintype "passive"))
      (node (ref "U4") (pin "4") (pinfunction "GND_4") (pintype "power_in"))
      (node (ref "U6") (pin "10") (pinfunction "RESV_10") (pintype "passive"))
      (node (ref "U6") (pin "11") (pinfunction "RESV_11") (pintype "passive"))
      (node (ref "U6") (pin "12") (pinfunction "RESV_12") (pintype "passive"))
      (node (ref "U6") (pin "13") (pinfunction "GND_13") (pintype "power_in"))
      (node (ref "U6") (pin "15") (pinfunction "RESV_15") (pintype "passive"))
      (node (ref "U6") (pin "8") (pinfunction "FSYNC_8") (pintype "input"))
      (node (ref "U6") (pin "9") (pinfunction "RESV_9") (pintype "passive"))
    )
    (net (code "45") (name "Net-(C4-Pad1)") (class "Default")
      (node (ref "C4") (pin "1") (pinfunction "1_1") (pintype "passive"))
      (node (ref "U2") (pin "48") (pinfunction "VCAP_48") (pintype "passive"))
    )
    (net (code "46") (name "Net-(C5-Pad1)") (class "Default")
      (node (ref "C5") (pin "1") (pinfunction "1_1") (pintype "passive"))
      (node (ref "U2") (pin "73") (pinfunction "VCAP_73") (pintype "passive"))
    )
    (net (code "47") (name "Net-(U2A-PC14-OSC32_IN)") (class "Default")
      (node (ref "C28") (pin "2") (pinfunction "2_2") (pintype "passive"))
      (node (ref "U2") (pin "8") (pinfunction "PC14-OSC32_IN_8") (pintype "bidirectional"))
      (node (ref "Y2") (pin "1") (pinfunction "1_1") (pintype "passive"))
    )
    (net (code "48") (name "Net-(U2A-PC15-OSC32_OUT)") (class "Default")
      (node (ref "C29") (pin "2") (pinfunction "2_2") (pintype "passive"))
      (node (ref "U2") (pin "9") (pinfunction "PC15-OSC32_OUT_9") (pintype "bidirectional"))
      (node (ref "Y2") (pin "2") (pinfunction "2_2") (pintype "passive"))
    )
    (net (code "49") (name "Net-(U2B-BOOT0)") (class "Default")
      (node (ref "R13") (pin "2") (pinfunction "2_2") (pintype "passive"))
      (node (ref "S1") (pin "2") (pinfunction "2_2") (pintype "passive"))
      (node (ref "U2") (pin "94") (pinfunction "BOOT0_94") (pintype "input"))
    )
    (net (code "50") (name "Net-(U2B-PH0-OSC_IN)") (class "Default")
      (node (ref "C25") (pin "2") (pinfunction "2_2") (pintype "passive"))
      (node (ref "U2") (pin "12") (pinfunction "PH0-OSC_IN_12") (pintype "bidirectional"))
      (node (ref "Y1") (pin "3") (pinfunction "3_3") (pintype "passive"))
    )
    (net (code "51") (name "Net-(U2B-PH1-OSC_OUT)") (class "Default")
      (node (ref "C26") (pin "2") (pinfunction "2_2") (pintype "passive"))
      (node (ref "U2") (pin "13") (pinfunction "PH1-OSC_OUT_13") (pintype "bidirectional"))
      (node (ref "Y1") (pin "1") (pinfunction "1_1") (pintype "passive"))
    )
    (net (code "52") (name "Net-(U2B-~{RST})") (class "Default")
      (node (ref "C27") (pin "1") (pinfunction "1_1") (pintype "passive"))
      (node (ref "R14") (pin "2") (pinfunction "2_2") (pintype "passive"))
      (node (ref "S2") (pin "1") (pinfunction "1_1") (pintype "passive"))
      (node (ref "U2") (pin "14") (pinfunction "~{RST}_14") (pintype "input"))
    )
    (net (code "53") (name "Net-(U4-{slash}HOLD{slash}RESET(IO3))") (class "Default")
      (node (ref "R16") (pin "1") (pinfunction "1_1") (pintype "passive"))
      (node (ref "U4") (pin "7") (pinfunction "/HOLD/RESET(IO3)_7") (pintype "bidirectional"))
    )
    (net (code "54") (name "Net-(U4-{slash}WP(IO2))") (class "Default")
      (node (ref "R15") (pin "1") (pinfunction "1_1") (pintype "passive"))
      (node (ref "U4") (pin "3") (pinfunction "/WP(IO2)_3") (pintype "bidirectional"))
    )
    (net (code "55") (name "Net-(U6A-CS)") (class "Default")
      (node (ref "R23") (pin "2") (pinfunction "2_2") (pintype "passive"))
      (node (ref "U6") (pin "5") (pinfunction "CS_5") (pintype "input"))
    )
    (net (code "56") (name "Net-(U6A-REGOUT)") (class "Default")
      (node (ref "C30") (pin "1") (pinfunction "1_1") (pintype "passive"))
      (node (ref "U6") (pin "14") (pinfunction "REGOUT_14") (pintype "passive"))
    )
    (net (code "57") (name "unconnected-(A1-SDO-Pad6)") (class "Default")
      (node (ref "A1") (pin "6") (pinfunction "SDO_6") (pintype "output"))
    )
    (net (code "58") (name "unconnected-(U2A-PA0-Pad22)") (class "Default")
      (node (ref "U2") (pin "22") (pinfunction "PA0_22") (pintype "bidirectional+no_connect"))
    )
    (net (code "59") (name "unconnected-(U2A-PA1-Pad23)") (class "Default")
      (node (ref "U2") (pin "23") (pinfunction "PA1_23") (pintype "bidirectional+no_connect"))
    )
    (net (code "60") (name "unconnected-(U2A-PA5-Pad29)") (class "Default")
      (node (ref "U2") (pin "29") (pinfunction "PA5_29") (pintype "bidirectional"))
    )
    (net (code "61") (name "unconnected-(U2A-PA6-Pad30)") (class "Default")
      (node (ref "U2") (pin "30") (pinfunction "PA6_30") (pintype "bidirectional"))
    )
    (net (code "62") (name "unconnected-(U2A-PA7-Pad31)") (class "Default")
      (node (ref "U2") (pin "31") (pinfunction "PA7_31") (pintype "bidirectional"))
    )
    (net (code "63") (name "unconnected-(U2A-PA8-Pad67)") (class "Default")
      (node (ref "U2") (pin "67") (pinfunction "PA8_67") (pintype "bidirectional+no_connect"))
    )
    (net (code "64") (name "unconnected-(U2A-PA9-Pad68)") (class "Default")
      (node (ref "U2") (pin "68") (pinfunction "PA9_68") (pintype "bidirectional"))
    )
    (net (code "65") (name "unconnected-(U2A-PA10-Pad69)") (class "Default")
      (node (ref "U2") (pin "69") (pinfunction "PA10_69") (pintype "bidirectional"))
    )
    (net (code "66") (name "unconnected-(U2A-PB0-Pad34)") (class "Default")
      (node (ref "U2") (pin "34") (pinfunction "PB0_34") (pintype "bidirectional+no_connect"))
    )
    (net (code "67") (name "unconnected-(U2A-PB2-Pad36)") (class "Default")
      (node (ref "U2") (pin "36") (pinfunction "PB2_36") (pintype "bidirectional"))
    )
    (net (code "68") (name "unconnected-(U2A-PB6-Pad92)") (class "Default")
      (node (ref "U2") (pin "92") (pinfunction "PB6_92") (pintype "bidirectional"))
    )
    (net (code "69") (name "unconnected-(U2A-PB7-Pad93)") (class "Default")
      (node (ref "U2") (pin "93") (pinfunction "PB7_93") (pintype "bidirectional"))
    )
    (net (code "70") (name "unconnected-(U2A-PC0-Pad15)") (class "Default")
      (node (ref "U2") (pin "15") (pinfunction "PC0_15") (pintype "bidirectional+no_connect"))
    )
    (net (code "71") (name "unconnected-(U2A-PC1-Pad16)") (class "Default")
      (node (ref "U2") (pin "16") (pinfunction "PC1_16") (pintype "bidirectional+no_connect"))
    )
    (net (code "72") (name "unconnected-(U2A-PC2_C-Pad17)") (class "Default")
      (node (ref "U2") (pin "17") (pinfunction "PC2_C_17") (pintype "bidirectional+no_connect"))
    )
    (net (code "73") (name "unconnected-(U2A-PC3_C-Pad18)") (class "Default")
      (node (ref "U2") (pin "18") (pinfunction "PC3_C_18") (pintype "bidirectional+no_connect"))
    )
    (net (code "74") (name "unconnected-(U2A-PC4-Pad32)") (class "Default")
      (node (ref "U2") (pin "32") (pinfunction "PC4_32") (pintype "bidirectional+no_connect"))
    )
    (net (code "75") (name "unconnected-(U2A-PC5-Pad33)") (class "Default")
      (node (ref "U2") (pin "33") (pinfunction "PC5_33") (pintype "bidirectional+no_connect"))
    )
    (net (code "76") (name "unconnected-(U2A-PC7-Pad64)") (class "Default")
      (node (ref "U2") (pin "64") (pinfunction "PC7_64") (pintype "bidirectional+no_connect"))
    )
    (net (code "77") (name "unconnected-(U2A-PC8-Pad65)") (class "Default")
      (node (ref "U2") (pin "65") (pinfunction "PC8_65") (pintype "bidirectional+no_connect"))
    )
    (net (code "78") (name "unconnected-(U2A-PC9-Pad66)") (class "Default")
      (node (ref "U2") (pin "66") (pinfunction "PC9_66") (pintype "bidirectional+no_connect"))
    )
    (net (code "79") (name "unconnected-(U2A-PC13-Pad7)") (class "Default")
      (node (ref "U2") (pin "7") (pinfunction "PC13_7") (pintype "bidirectional"))
    )
    (net (code "80") (name "unconnected-(U2B-PD0-Pad81)") (class "Default")
      (node (ref "U2") (pin "81") (pinfunction "PD0_81") (pintype "bidirectional+no_connect"))
    )
    (net (code "81") (name "unconnected-(U2B-PD10-Pad57)") (class "Default")
      (node (ref "U2") (pin "57") (pinfunction "PD10_57") (pintype "bidirectional+no_connect"))
    )
    (net (code "82") (name "unconnected-(U2B-PD11-Pad58)") (class "Default")
      (node (ref "U2") (pin "58") (pinfunction "PD11_58") (pintype "bidirectional+no_connect"))
    )
    (net (code "83") (name "unconnected-(U2B-PE0-Pad97)") (class "Default")
      (node (ref "U2") (pin "97") (pinfunction "PE0_97") (pintype "input"))
    )
    (net (code "84") (name "unconnected-(U2B-PE2-Pad1)") (class "Default")
      (node (ref "U2") (pin "1") (pinfunction "PE2_1") (pintype "input+no_connect"))
    )
    (net (code "85") (name "unconnected-(U2B-PE4-Pad3)") (class "Default")
      (node (ref "U2") (pin "3") (pinfunction "PE4_3") (pintype "bidirectional+no_connect"))
    )
    (net (code "86") (name "unconnected-(U2B-PE5-Pad4)") (class "Default")
      (node (ref "U2") (pin "4") (pinfunction "PE5_4") (pintype "bidirectional+no_connect"))
    )
    (net (code "87") (name "unconnected-(U2B-PE6-Pad5)") (class "Default")
      (node (ref "U2") (pin "5") (pinfunction "PE6_5") (pintype "bidirectional+no_connect"))
    )
    (net (code "88") (name "unconnected-(U2B-PE9-Pad39)") (class "Default")
      (node (ref "U2") (pin "39") (pinfunction "PE9_39") (pintype "output+no_connect"))
    )
    (net (code "89") (name "unconnected-(U2B-PE10-Pad40)") (class "Default")
      (node (ref "U2") (pin "40") (pinfunction "PE10_40") (pintype "output+no_connect"))
    )
    (net (code "90") (name "unconnected-(U2B-PE11-Pad41)") (class "Default")
      (node (ref "U2") (pin "41") (pinfunction "PE11_41") (pintype "output+no_connect"))
    )
    (net (code "91") (name "unconnected-(U2B-PE12-Pad42)") (class "Default")
      (node (ref "U2") (pin "42") (pinfunction "PE12_42") (pintype "bidirectional+no_connect"))
    )
    (net (code "92") (name "unconnected-(U2B-PE13-Pad43)") (class "Default")
      (node (ref "U2") (pin "43") (pinfunction "PE13_43") (pintype "input+no_connect"))
    )
    (net (code "93") (name "unconnected-(U2B-PE14-Pad44)") (class "Default")
      (node (ref "U2") (pin "44") (pinfunction "PE14_44") (pintype "output+no_connect"))
    )
    (net (code "94") (name "unconnected-(U2B-PE15-Pad45)") (class "Default")
      (node (ref "U2") (pin "45") (pinfunction "PE15_45") (pintype "output+no_connect"))
    )
    (net (code "95") (name "unconnected-(U6B-RESV-Pad7)") (class "Default")
      (node (ref "U6") (pin "7") (pinfunction "RESV_7") (pintype "passive"))
    )
  )
)
